# badge.net
KiCad netlist of a schematic drawn in EAGLE
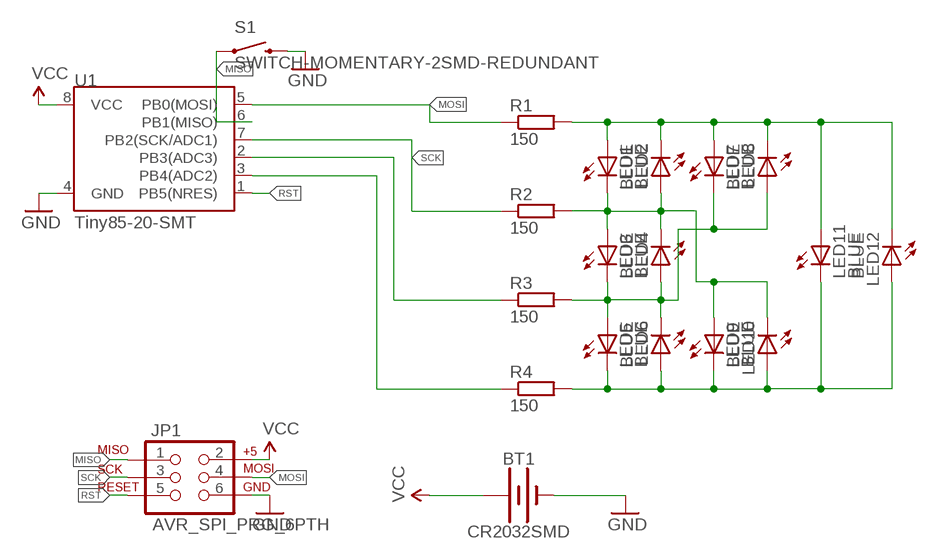
[diagram p0: schematic, sheet 1]

(export (version "E")
  (design (tool "Eeschema 10.0.6"))
  (components
    (comp (ref "BT1")
      (value "CR2032SMD")
      (footprint "eagle-import:BATTCON_20MM_4LEGS")
      (libsource (lib "eagle-import") (part "BATTERY-20MM_SMD_4LEGS"))
    )
    (comp (ref "JP1")
      (value "AVR_SPI_PRG_6PTH")
      (footprint "eagle-import:2X3")
      (libsource (lib "eagle-import") (part "AVR_SPI_PRG_6PTH"))
    )
    (comp (ref "LED1")
      (value "BLUE")
      (footprint "eagle-import:CHIP-LED0805")
      (libsource (lib "eagle-import") (part "LEDCHIP-LED0805"))
    )
    (comp (ref "LED2")
      (value "BLUE")
      (footprint "eagle-import:CHIP-LED0805")
      (libsource (lib "eagle-import") (part "LEDCHIP-LED0805"))
    )
    (comp (ref "LED3")
      (value "BLUE")
      (footprint "eagle-import:CHIP-LED0805")
      (libsource (lib "eagle-import") (part "LEDCHIP-LED0805"))
    )
    (comp (ref "LED4")
      (value "BLUE")
      (footprint "eagle-import:CHIP-LED0805")
      (libsource (lib "eagle-import") (part "LEDCHIP-LED0805"))
    )
    (comp (ref "LED5")
      (value "BLUE")
      (footprint "eagle-import:CHIP-LED0805")
      (libsource (lib "eagle-import") (part "LEDCHIP-LED0805"))
    )
    (comp (ref "LED6")
      (value "BLUE")
      (footprint "eagle-import:CHIP-LED0805")
      (libsource (lib "eagle-import") (part "LEDCHIP-LED0805"))
    )
    (comp (ref "LED7")
      (value "BLUE")
      (footprint "eagle-import:CHIP-LED0805")
      (libsource (lib "eagle-import") (part "LEDCHIP-LED0805"))
    )
    (comp (ref "LED8")
      (value "BLUE")
      (footprint "eagle-import:CHIP-LED0805")
      (libsource (lib "eagle-import") (part "LEDCHIP-LED0805"))
    )
    (comp (ref "LED9")
      (value "BLUE")
      (footprint "eagle-import:CHIP-LED0805")
      (libsource (lib "eagle-import") (part "LEDCHIP-LED0805"))
    )
    (comp (ref "LED10")
      (value "BLUE")
      (footprint "eagle-import:CHIP-LED0805")
      (libsource (lib "eagle-import") (part "LEDCHIP-LED0805"))
    )
    (comp (ref "LED11")
      (value "BLUE")
      (footprint "eagle-import:CHIP-LED0805")
      (libsource (lib "eagle-import") (part "LEDCHIP-LED0805"))
    )
    (comp (ref "LED12")
      (value "BLUE")
      (footprint "eagle-import:CHIP-LED0805")
      (libsource (lib "eagle-import") (part "LEDCHIP-LED0805"))
    )
    (comp (ref "R1")
      (value "150")
      (footprint "eagle-import:R0805")
      (libsource (lib "eagle-import") (part "R-EU_R0805"))
    )
    (comp (ref "R2")
      (value "150")
      (footprint "eagle-import:R0805")
      (libsource (lib "eagle-import") (part "R-EU_R0805"))
    )
    (comp (ref "R3")
      (value "150")
      (footprint "eagle-import:R0805")
      (libsource (lib "eagle-import") (part "R-EU_R0805"))
    )
    (comp (ref "R4")
      (value "150")
      (footprint "eagle-import:R0805")
      (libsource (lib "eagle-import") (part "R-EU_R0805"))
    )
    (comp (ref "S1")
      (value "SWITCH-MOMENTARY-2SMD-REDUNDANT")
      (footprint "eagle-import:TACTILE-SWITCH-SMD")
      (libsource (lib "eagle-import") (part "SWITCH-MOMENTARY-2SMD-REDUNDANT"))
    )
    (comp (ref "U1")
      (value "Tiny85-20-SMT")
      (footprint "eagle-import:SO08-EIAJ")
      (libsource (lib "eagle-import") (part "ATTINY45TINY85-20-SMT"))
    )
  )
  (nets
    (net (code "1") (name "GND") (class "Default")
      (node (ref "BT1") (pin "NEGATIVE") (pinfunction "GND_NEGATIVE") (pintype "power_in"))
      (node (ref "JP1") (pin "6") (pinfunction "6_6") (pintype "passive"))
      (node (ref "S1") (pin "3") (pinfunction "2_3") (pintype "passive"))
      (node (ref "S1") (pin "4") (pinfunction "2_4") (pintype "passive"))
      (node (ref "U1") (pin "4") (pinfunction "GND_4") (pintype "bidirectional"))
    )
    (net (code "2") (name "MISO") (class "Default")
      (node (ref "JP1") (pin "1") (pinfunction "1_1") (pintype "passive"))
      (node (ref "S1") (pin "1") (pinfunction "1_1") (pintype "passive"))
      (node (ref "S1") (pin "2") (pinfunction "1_2") (pintype "passive"))
      (node (ref "U1") (pin "6") (pinfunction "PB1(MISO)_6") (pintype "bidirectional"))
    )
    (net (code "3") (name "MOSI") (class "Default")
      (node (ref "JP1") (pin "4") (pinfunction "4_4") (pintype "passive"))
      (node (ref "R1") (pin "1") (pinfunction "1_1") (pintype "passive"))
      (node (ref "U1") (pin "5") (pinfunction "PB0(MOSI)_5") (pintype "bidirectional"))
    )
    (net (code "4") (name "Net-(LED1-PadA)") (class "Default")
      (node (ref "LED1") (pin "A") (pinfunction "A_A") (pintype "passive"))
      (node (ref "LED11") (pin "A") (pinfunction "A_A") (pintype "passive"))
      (node (ref "LED12") (pin "C") (pinfunction "C_C") (pintype "passive"))
      (node (ref "LED2") (pin "C") (pinfunction "C_C") (pintype "passive"))
      (node (ref "LED7") (pin "A") (pinfunction "A_A") (pintype "passive"))
      (node (ref "LED8") (pin "C") (pinfunction "C_C") (pintype "passive"))
      (node (ref "R1") (pin "2") (pinfunction "2_2") (pintype "passive"))
    )
    (net (code "5") (name "Net-(LED1-PadC)") (class "Default")
      (node (ref "LED1") (pin "C") (pinfunction "C_C") (pintype "passive"))
      (node (ref "LED10") (pin "C") (pinfunction "C_C") (pintype "passive"))
      (node (ref "LED2") (pin "A") (pinfunction "A_A") (pintype "passive"))
      (node (ref "LED3") (pin "A") (pinfunction "A_A") (pintype "passive"))
      (node (ref "LED4") (pin "C") (pinfunction "C_C") (pintype "passive"))
      (node (ref "LED9") (pin "A") (pinfunction "A_A") (pintype "passive"))
      (node (ref "R2") (pin "2") (pinfunction "2_2") (pintype "passive"))
    )
    (net (code "6") (name "Net-(LED3-PadC)") (class "Default")
      (node (ref "LED3") (pin "C") (pinfunction "C_C") (pintype "passive"))
      (node (ref "LED4") (pin "A") (pinfunction "A_A") (pintype "passive"))
      (node (ref "LED5") (pin "A") (pinfunction "A_A") (pintype "passive"))
      (node (ref "LED6") (pin "C") (pinfunction "C_C") (pintype "passive"))
      (node (ref "LED7") (pin "C") (pinfunction "C_C") (pintype "passive"))
      (node (ref "LED8") (pin "A") (pinfunction "A_A") (pintype "passive"))
      (node (ref "R3") (pin "2") (pinfunction "2_2") (pintype "passive"))
    )
    (net (code "7") (name "Net-(LED10-PadA)") (class "Default")
      (node (ref "LED10") (pin "A") (pinfunction "A_A") (pintype "passive"))
      (node (ref "LED11") (pin "C") (pinfunction "C_C") (pintype "passive"))
      (node (ref "LED12") (pin "A") (pinfunction "A_A") (pintype "passive"))
      (node (ref "LED5") (pin "C") (pinfunction "C_C") (pintype "passive"))
      (node (ref "LED6") (pin "A") (pinfunction "A_A") (pintype "passive"))
      (node (ref "LED9") (pin "C") (pinfunction "C_C") (pintype "passive"))
      (node (ref "R4") (pin "2") (pinfunction "2_2") (pintype "passive"))
    )
    (net (code "8") (name "Net-(U1-PB3(ADC3))") (class "Default")
      (node (ref "R3") (pin "1") (pinfunction "1_1") (pintype "passive"))
      (node (ref "U1") (pin "2") (pinfunction "PB3(ADC3)_2") (pintype "bidirectional"))
    )
    (net (code "9") (name "Net-(U1-PB4(ADC2))") (class "Default")
      (node (ref "R4") (pin "1") (pinfunction "1_1") (pintype "passive"))
      (node (ref "U1") (pin "3") (pinfunction "PB4(ADC2)_3") (pintype "bidirectional"))
    )
    (net (code "10") (name "RST") (class "Default")
      (node (ref "JP1") (pin "5") (pinfunction "5_5") (pintype "passive"))
      (node (ref "U1") (pin "1") (pinfunction "PB5(NRES)_1") (pintype "bidirectional"))
    )
    (net (code "11") (name "SCK") (class "Default")
      (node (ref "JP1") (pin "3") (pinfunction "3_3") (pintype "passive"))
      (node (ref "R2") (pin "1") (pinfunction "1_1") (pintype "passive"))
      (node (ref "U1") (pin "7") (pinfunction "PB2(SCK/ADC1)_7") (pintype "bidirectional"))
    )
    (net (code "12") (name "VCC") (class "Default")
      (node (ref "BT1") (pin "POSITIVE@1") (pinfunction "VCC_POSITIVE@1") (pintype "power_in"))
      (node (ref "BT1") (pin "POSITIVE@2") (pinfunction "VCC_POSITIVE@2") (pintype "power_in"))
      (node (ref "BT1") (pin "POSITIVE@3") (pinfunction "VCC_POSITIVE@3") (pintype "power_in"))
      (node (ref "BT1") (pin "POSITIVE@4") (pinfunction "VCC_POSITIVE@4") (pintype "power_in"))
      (node (ref "JP1") (pin "2") (pinfunction "2_2") (pintype "passive"))
      (node (ref "U1") (pin "8") (pinfunction "VCC_8") (pintype "bidirectional"))
    )
  )
)
